# MCU.net
KiCad netlist of a schematic drawn in Altium Designer
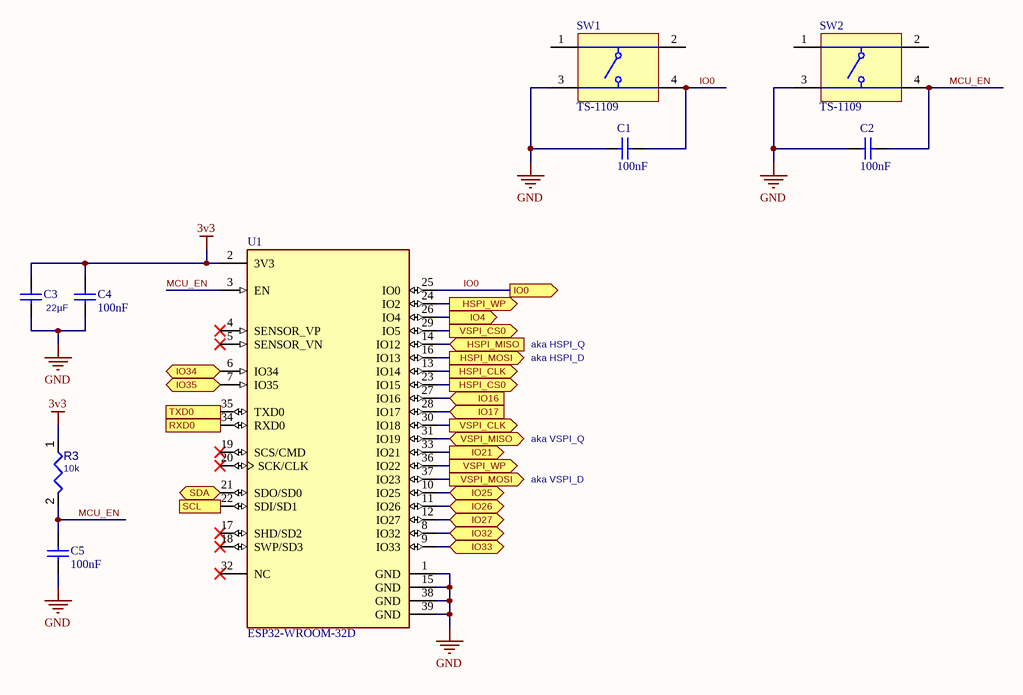
[diagram p0: MCU.SchDoc]

(export (version "E")
  (design (tool "Eeschema 10.0.6"))
  (components
    (comp (ref "C1")
      (value "GRM155R71E104KE14D")
      (footprint "Capacitor_0402")
      (description "Chip Capacitor 100nF 0402 25V X7R")
      (fields (field (name "CAPACITANCE") "100nF") (field (name "JLCPCB PART #") "C1525"))
      (libsource (lib "RIT Launch Initiative") (part "CAPACITOR"))
    )
    (comp (ref "C2")
      (value "GRM155R71E104KE14D")
      (footprint "Capacitor_0402")
      (description "Chip Capacitor 100nF 0402 25V X7R")
      (fields (field (name "CAPACITANCE") "100nF"))
      (libsource (lib "RIT Launch Initiative") (part "CAPACITOR"))
    )
    (comp (ref "C3")
      (value "22µF")
      (footprint "Capacitor_0603")
      (description "Chip Capacitor 22UF 6.3V X5R 0603")
      (fields (field (name "JLCPCB PART #") "C59461") (field (name "Comment") "CL10A226MQ8NRNC"))
      (libsource (lib "RIT Launch Initiative") (part "CAPACITOR"))
    )
    (comp (ref "C4")
      (value "GRM155R71E104KE14D")
      (footprint "Capacitor_0402")
      (description "Chip Capacitor 100nF 0402 25V X7R")
      (fields (field (name "CAPACITANCE") "100nF"))
      (libsource (lib "RIT Launch Initiative") (part "CAPACITOR"))
    )
    (comp (ref "C5")
      (value "GRM155R71E104KE14D")
      (footprint "Capacitor_0402")
      (description "Chip Capacitor 100nF 0402 25V X7R")
      (fields (field (name "CAPACITANCE") "100nF"))
      (libsource (lib "RIT Launch Initiative") (part "CAPACITOR"))
    )
    (comp (ref "R3")
      (value "10k")
      (footprint "RESC0402(1005)_L")
      (description "Chip Resistor, 10 kOhms, +/-1 %, 63 mW, -55 to 125 degC, 0402")
      (fields (field (name "POWER") "63mW") (field (name "TOLERANCE") "1%"))
      (libsource (lib "RIT Launch Initiative") (part "RES-2"))
    )
    (comp (ref "SW1")
      (value "TS-1109")
      (footprint "BEST-TS-1109_V")
      (description "Tactile Switch, SPST, 12 V, 50 mA, -20 to 80 degC, 4-Pin THD")
      (fields (field (name "MANUFACTURER") "Shenzhen Best"))
      (libsource (lib "RIT Launch Initiative") (part "SW-SPST-4_A"))
    )
    (comp (ref "SW2")
      (value "TS-1109")
      (footprint "BEST-TS-1109_V")
      (description "Tactile Switch, SPST, 12 V, 50 mA, -20 to 80 degC, 4-Pin THD")
      (fields (field (name "MANUFACTURER") "Shenzhen Best"))
      (libsource (lib "RIT Launch Initiative") (part "SW-SPST-4_A"))
    )
    (comp (ref "U1")
      (value "ESP32-WROOM-32D")
      (footprint "ESP32-WROOM-32D-Footprint-1")
      (libsource (lib "RIT Launch Initiative") (part "ESP32-WROOM-32D"))
    )
  )
  (nets
    (net (code "1") (name "/HSPI_CLK") (class "Default")
      (node (ref "U1") (pin "13") (pinfunction "IO14_13") (pintype "bidirectional"))
    )
    (net (code "2") (name "/HSPI_CS0") (class "Default")
      (node (ref "U1") (pin "23") (pinfunction "IO15_23") (pintype "bidirectional"))
    )
    (net (code "3") (name "/HSPI_MISO") (class "Default")
      (node (ref "U1") (pin "14") (pinfunction "IO12_14") (pintype "bidirectional"))
    )
    (net (code "4") (name "/HSPI_MOSI") (class "Default")
      (node (ref "U1") (pin "16") (pinfunction "IO13_16") (pintype "bidirectional"))
    )
    (net (code "5") (name "/HSPI_WP") (class "Default")
      (node (ref "U1") (pin "24") (pinfunction "IO2_24") (pintype "bidirectional"))
    )
    (net (code "6") (name "/IO0") (class "Default")
      (node (ref "C1") (pin "1") (pinfunction "1_1") (pintype "passive"))
      (node (ref "SW1") (pin "4") (pinfunction "4_4") (pintype "passive"))
      (node (ref "U1") (pin "25") (pinfunction "IO0_25") (pintype "bidirectional"))
    )
    (net (code "7") (name "/IO4") (class "Default")
      (node (ref "U1") (pin "26") (pinfunction "IO4_26") (pintype "bidirectional"))
    )
    (net (code "8") (name "/IO16") (class "Default")
      (node (ref "U1") (pin "27") (pinfunction "IO16_27") (pintype "bidirectional"))
    )
    (net (code "9") (name "/IO17") (class "Default")
      (node (ref "U1") (pin "28") (pinfunction "IO17_28") (pintype "bidirectional"))
    )
    (net (code "10") (name "/IO21") (class "Default")
      (node (ref "U1") (pin "33") (pinfunction "IO21_33") (pintype "bidirectional"))
    )
    (net (code "11") (name "/IO25") (class "Default")
      (node (ref "U1") (pin "10") (pinfunction "IO25_10") (pintype "bidirectional"))
    )
    (net (code "12") (name "/IO26") (class "Default")
      (node (ref "U1") (pin "11") (pinfunction "IO26_11") (pintype "bidirectional"))
    )
    (net (code "13") (name "/IO27") (class "Default")
      (node (ref "U1") (pin "12") (pinfunction "IO27_12") (pintype "bidirectional"))
    )
    (net (code "14") (name "/IO32") (class "Default")
      (node (ref "U1") (pin "8") (pinfunction "IO32_8") (pintype "bidirectional"))
    )
    (net (code "15") (name "/IO33") (class "Default")
      (node (ref "U1") (pin "9") (pinfunction "IO33_9") (pintype "bidirectional"))
    )
    (net (code "16") (name "/IO34") (class "Default")
      (node (ref "U1") (pin "6") (pinfunction "IO34_6") (pintype "input"))
    )
    (net (code "17") (name "/IO35") (class "Default")
      (node (ref "U1") (pin "7") (pinfunction "IO35_7") (pintype "input"))
    )
    (net (code "18") (name "/MCU_EN") (class "Default")
      (node (ref "C2") (pin "1") (pinfunction "1_1") (pintype "passive"))
      (node (ref "C5") (pin "2") (pinfunction "2_2") (pintype "passive"))
      (node (ref "R3") (pin "2") (pinfunction "2_2") (pintype "passive"))
      (node (ref "SW2") (pin "4") (pinfunction "4_4") (pintype "passive"))
      (node (ref "U1") (pin "3") (pinfunction "EN_3") (pintype "input"))
    )
    (net (code "19") (name "/RXD0") (class "Default")
      (node (ref "U1") (pin "34") (pinfunction "RXD0_34") (pintype "bidirectional"))
    )
    (net (code "20") (name "/SCL") (class "Default")
      (node (ref "U1") (pin "22") (pinfunction "SDI/SD1_22") (pintype "bidirectional"))
    )
    (net (code "21") (name "/SDA") (class "Default")
      (node (ref "U1") (pin "21") (pinfunction "SDO/SD0_21") (pintype "bidirectional"))
    )
    (net (code "22") (name "/TXD0") (class "Default")
      (node (ref "U1") (pin "35") (pinfunction "TXD0_35") (pintype "bidirectional"))
    )
    (net (code "23") (name "/VSPI_CLK") (class "Default")
      (node (ref "U1") (pin "30") (pinfunction "IO18_30") (pintype "bidirectional"))
    )
    (net (code "24") (name "/VSPI_CS0") (class "Default")
      (node (ref "U1") (pin "29") (pinfunction "IO5_29") (pintype "bidirectional"))
    )
    (net (code "25") (name "/VSPI_MISO") (class "Default")
      (node (ref "U1") (pin "31") (pinfunction "IO19_31") (pintype "bidirectional"))
    )
    (net (code "26") (name "/VSPI_MOSI") (class "Default")
      (node (ref "U1") (pin "37") (pinfunction "IO23_37") (pintype "bidirectional"))
    )
    (net (code "27") (name "/VSPI_WP") (class "Default")
      (node (ref "U1") (pin "36") (pinfunction "IO22_36") (pintype "bidirectional"))
    )
    (net (code "28") (name "3v3") (class "Default")
      (node (ref "C3") (pin "2") (pinfunction "2_2") (pintype "passive"))
      (node (ref "C4") (pin "2") (pinfunction "2_2") (pintype "passive"))
      (node (ref "R3") (pin "1") (pinfunction "1_1") (pintype "passive"))
      (node (ref "U1") (pin "2") (pinfunction "3V3_2") (pintype "power_in"))
    )
    (net (code "29") (name "GND") (class "Default")
      (node (ref "C1") (pin "2") (pinfunction "2_2") (pintype "passive"))
      (node (ref "C2") (pin "2") (pinfunction "2_2") (pintype "passive"))
      (node (ref "C3") (pin "1") (pinfunction "1_1") (pintype "passive"))
      (node (ref "C4") (pin "1") (pinfunction "1_1") (pintype "passive"))
      (node (ref "C5") (pin "1") (pinfunction "1_1") (pintype "passive"))
      (node (ref "SW1") (pin "3") (pinfunction "3_3") (pintype "passive"))
      (node (ref "SW2") (pin "3") (pinfunction "3_3") (pintype "passive"))
      (node (ref "U1") (pin "1") (pinfunction "GND_1") (pintype "power_in"))
      (node (ref "U1") (pin "15") (pinfunction "GND_15") (pintype "power_in"))
      (node (ref "U1") (pin "38") (pinfunction "GND_38") (pintype "power_in"))
      (node (ref "U1") (pin "39") (pinfunction "GND_39") (pintype "power_in"))
    )
    (net (code "30") (name "unconnected-(SW1-Pad1)") (class "Default")
      (node (ref "SW1") (pin "1") (pinfunction "1_1") (pintype "passive"))
    )
    (net (code "31") (name "unconnected-(SW1-Pad2)") (class "Default")
      (node (ref "SW1") (pin "2") (pinfunction "2_2") (pintype "passive"))
    )
    (net (code "32") (name "unconnected-(SW2-Pad1)") (class "Default")
      (node (ref "SW2") (pin "1") (pinfunction "1_1") (pintype "passive"))
    )
    (net (code "33") (name "unconnected-(SW2-Pad2)") (class "Default")
      (node (ref "SW2") (pin "2") (pinfunction "2_2") (pintype "passive"))
    )
    (net (code "34") (name "unconnected-(U1-NC-Pad32)") (class "Default")
      (node (ref "U1") (pin "32") (pinfunction "NC_32") (pintype "open_emitter+no_connect"))
    )
    (net (code "35") (name "unconnected-(U1-SCK{slash}CLK-Pad20)") (class "Default")
      (node (ref "U1") (pin "20") (pinfunction "SCK/CLK_20") (pintype "bidirectional+no_connect"))
    )
    (net (code "36") (name "unconnected-(U1-SCS{slash}CMD-Pad19)") (class "Default")
      (node (ref "U1") (pin "19") (pinfunction "SCS/CMD_19") (pintype "bidirectional+no_connect"))
    )
    (net (code "37") (name "unconnected-(U1-SENSOR_VN-Pad5)") (class "Default")
      (node (ref "U1") (pin "5") (pinfunction "SENSOR_VN_5") (pintype "input+no_connect"))
    )
    (net (code "38") (name "unconnected-(U1-SENSOR_VP-Pad4)") (class "Default")
      (node (ref "U1") (pin "4") (pinfunction "SENSOR_VP_4") (pintype "input+no_connect"))
    )
    (net (code "39") (name "unconnected-(U1-SHD{slash}SD2-Pad17)") (class "Default")
      (node (ref "U1") (pin "17") (pinfunction "SHD/SD2_17") (pintype "bidirectional+no_connect"))
    )
    (net (code "40") (name "unconnected-(U1-SWP{slash}SD3-Pad18)") (class "Default")
      (node (ref "U1") (pin "18") (pinfunction "SWP/SD3_18") (pintype "bidirectional+no_connect"))
    )
  )
)
